# STM32F401R.net
KiCad netlist of a schematic drawn in Altium Designer
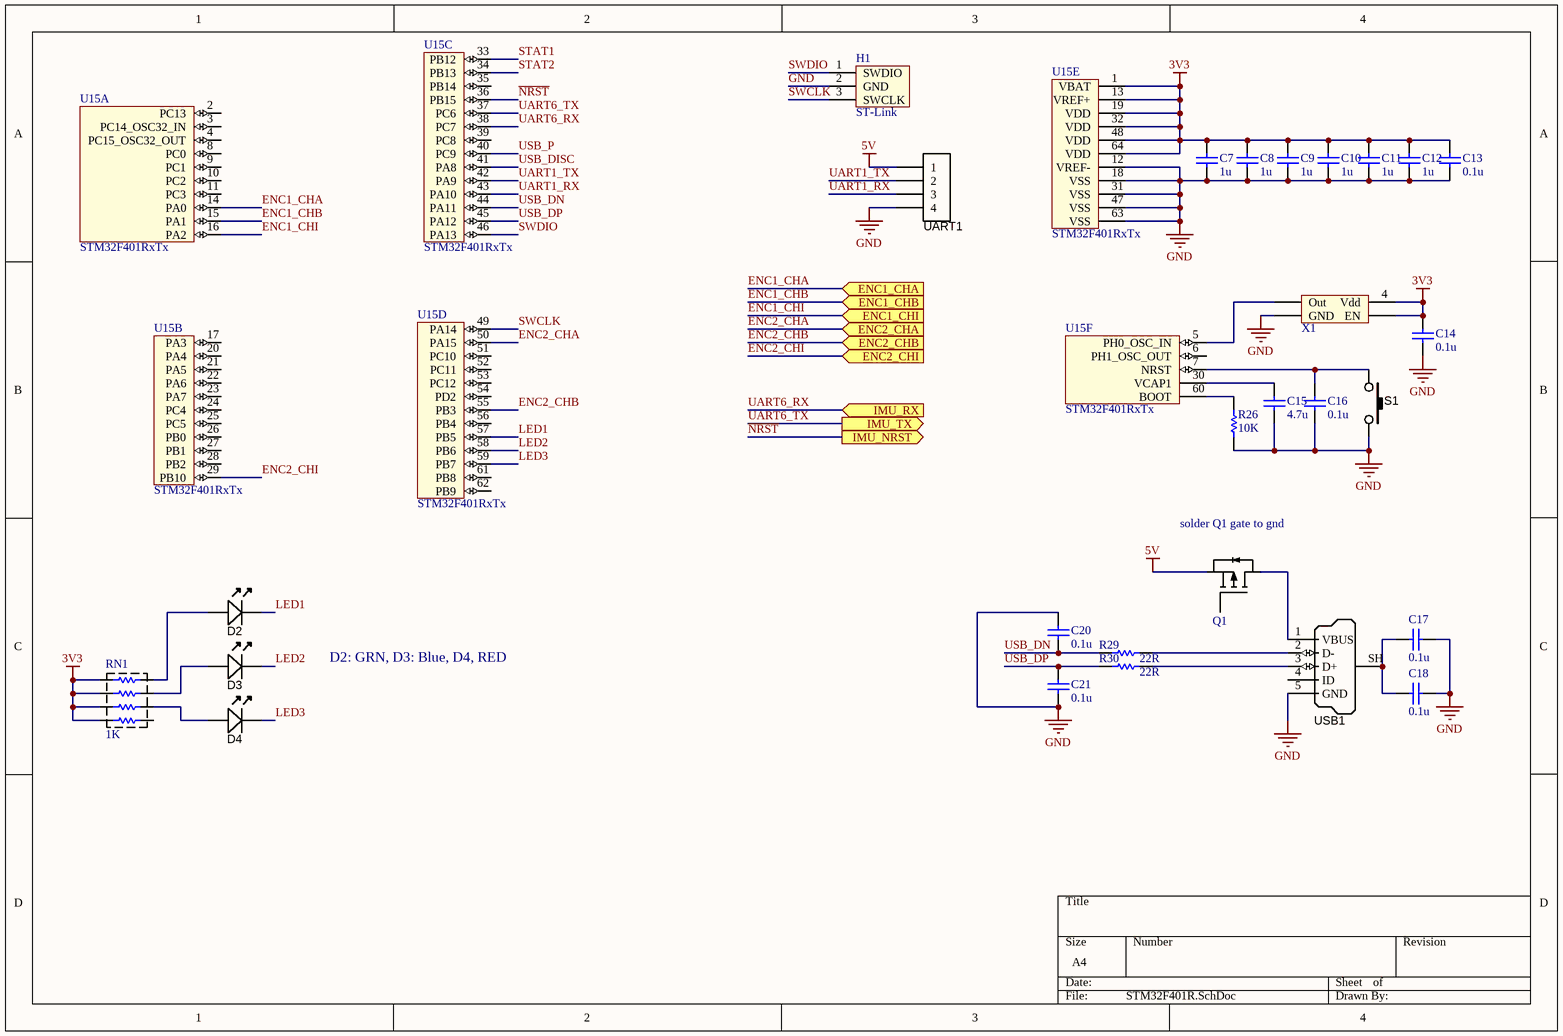
[diagram p0: STM32F401R.SchDoc]

(export (version "E")
  (design (tool "Eeschema 10.0.6"))
  (components
    (comp (ref "C7")
      (value "1u")
      (footprint "CAPC1608X90N")
      (description "Capacitor")
      (fields (field (name "Comment") "Cap") (field (name "PUBLISHER") "Altium Limited"))
      (libsource (lib "IOBoard_Low") (part "Cap"))
    )
    (comp (ref "C8")
      (value "1u")
      (footprint "CAPC1608X90N")
      (description "Capacitor")
      (fields (field (name "Comment") "Cap") (field (name "PUBLISHER") "Altium Limited"))
      (libsource (lib "IOBoard_Low") (part "Cap"))
    )
    (comp (ref "C9")
      (value "1u")
      (footprint "CAPC1608X90N")
      (description "Capacitor")
      (fields (field (name "Comment") "Cap") (field (name "PUBLISHER") "Altium Limited"))
      (libsource (lib "IOBoard_Low") (part "Cap"))
    )
    (comp (ref "C10")
      (value "1u")
      (footprint "CAPC1608X90N")
      (description "Capacitor")
      (fields (field (name "Comment") "Cap") (field (name "PUBLISHER") "Altium Limited"))
      (libsource (lib "IOBoard_Low") (part "Cap"))
    )
    (comp (ref "C11")
      (value "1u")
      (footprint "CAPC1608X90N")
      (description "Capacitor")
      (fields (field (name "Comment") "Cap") (field (name "PUBLISHER") "Altium Limited"))
      (libsource (lib "IOBoard_Low") (part "Cap"))
    )
    (comp (ref "C12")
      (value "1u")
      (footprint "CAPC1608X90N")
      (description "Capacitor")
      (fields (field (name "Comment") "Cap") (field (name "PUBLISHER") "Altium Limited"))
      (libsource (lib "IOBoard_Low") (part "Cap"))
    )
    (comp (ref "C13")
      (value "0.1u")
      (footprint "CAPC1608X90N")
      (description "Capacitor")
      (fields (field (name "Comment") "Cap") (field (name "PUBLISHER") "Altium Limited"))
      (libsource (lib "IOBoard_Low") (part "Cap"))
    )
    (comp (ref "C14")
      (value "0.1u")
      (footprint "CAPC1608X90N")
      (description "Capacitor")
      (fields (field (name "Comment") "Cap") (field (name "PUBLISHER") "Altium Limited"))
      (libsource (lib "IOBoard_Low") (part "Cap"))
    )
    (comp (ref "C15")
      (value "4.7u")
      (footprint "CAPC1608X90N")
      (description "Capacitor")
      (fields (field (name "Comment") "Cap") (field (name "PUBLISHER") "Altium Limited"))
      (libsource (lib "IOBoard_Low") (part "Cap"))
    )
    (comp (ref "C16")
      (value "0.1u")
      (footprint "CAPC1608X90N")
      (description "Capacitor")
      (fields (field (name "Comment") "Cap") (field (name "PUBLISHER") "Altium Limited"))
      (libsource (lib "IOBoard_Low") (part "Cap"))
    )
    (comp (ref "C17")
      (value "0.1u")
      (footprint "CAPC1608X90N")
      (description "Capacitor")
      (fields (field (name "Comment") "Cap") (field (name "PUBLISHER") "Altium Limited"))
      (libsource (lib "IOBoard_Low") (part "Cap"))
    )
    (comp (ref "C18")
      (value "0.1u")
      (footprint "CAPC1608X90N")
      (description "Capacitor")
      (fields (field (name "Comment") "Cap") (field (name "PUBLISHER") "Altium Limited"))
      (libsource (lib "IOBoard_Low") (part "Cap"))
    )
    (comp (ref "C20")
      (value "0.1u")
      (footprint "CAPC1608X90N")
      (description "Capacitor")
      (fields (field (name "Comment") "Cap") (field (name "PUBLISHER") "Altium Limited"))
      (libsource (lib "IOBoard_Low") (part "Cap"))
    )
    (comp (ref "C21")
      (value "0.1u")
      (footprint "CAPC1608X90N")
      (description "Capacitor")
      (fields (field (name "Comment") "Cap") (field (name "PUBLISHER") "Altium Limited"))
      (libsource (lib "IOBoard_Low") (part "Cap"))
    )
    (comp (ref "D2")
      (value "LED_Green_GullWing")
      (footprint "LED-0805-A")
      (description "LED Gull-wing SMD High-intensity Green 450mcd 574nm")
      (libsource (lib "IOBoard") (part "LED_Green_GullWing"))
    )
    (comp (ref "D3")
      (value "LED_Green_GullWing")
      (footprint "LED-0805-A")
      (description "LED Gull-wing SMD High-intensity Green 450mcd 574nm")
      (libsource (lib "IOBoard") (part "LED_Green_GullWing"))
    )
    (comp (ref "D4")
      (value "LED_Green_GullWing")
      (footprint "LED-0805-A")
      (description "LED Gull-wing SMD High-intensity Green 450mcd 574nm")
      (libsource (lib "IOBoard") (part "LED_Green_GullWing"))
    )
    (comp (ref "H1")
      (value "ST-Link")
      (footprint "ST-Link")
      (description "ST-Link header with silkscreen")
      (libsource (lib "IOBoard") (part "ST-Link"))
    )
    (comp (ref "Q1")
      (value "DMP4010SK3Q")
      (footprint "TO-252")
      (libsource (lib "IOBoard_Low") (part "DMP4010SK3Q"))
    )
    (comp (ref "R26")
      (value "10K")
      (footprint "RESC1608X55N")
      (description "Resistor")
      (fields (field (name "Comment") "Res1") (field (name "PUBLISHER") "Altium Limited"))
      (libsource (lib "IOBoard_Low") (part "Res1"))
    )
    (comp (ref "R29")
      (value "22R")
      (footprint "RESC1608X55N")
      (description "Resistor")
      (fields (field (name "Comment") "Res1") (field (name "PUBLISHER") "Altium Limited"))
      (libsource (lib "IOBoard_Low") (part "Res1"))
    )
    (comp (ref "R30")
      (value "22R")
      (footprint "RESC1608X55N")
      (description "Resistor")
      (fields (field (name "Comment") "Res1") (field (name "PUBLISHER") "Altium Limited"))
      (libsource (lib "IOBoard_Low") (part "Res1"))
    )
    (comp (ref "RN1")
      (value "1K")
      (footprint "RESCAXS50P160X320X70-8N")
      (fields (field (name "Comment") "resistor network"))
      (libsource (lib "IOBoard") (part "RES_NET"))
    )
    (comp (ref "S1")
      (value "SW_THT_PB_4.3mm")
      (footprint "TACT_SWT-SMD-4.4")
      (description "Switch, tact, 4.3mm stem")
      (libsource (lib "IOBoard") (part "SW_THT_PB_4.3mm"))
    )
    (comp (ref "U15")
      (value "STM32F401RxTx")
      (footprint "LQFP64")
      (libsource (lib "IOBoard") (part "STM32F401RxTx"))
    )
    (comp (ref "UART1")
      (value "Programmer")
      (footprint "HDR1X4_2.54MMP")
      (description "Header 4-pin")
      (libsource (lib "IOBoard") (part "Header4P"))
    )
    (comp (ref "USB1")
      (value "USB Micro Type B")
      (footprint "USB_MICRO-B")
      (description "Connector SMD USB Micro Type B middle mount")
      (libsource (lib "IOBoard") (part "USB_Micro_TypeB"))
    )
    (comp (ref "X1")
      (value "ASV-8.000MHZ-EJ-T")
      (footprint "ASV SERIES")
      (description "3.3Vdc HCMOS SMD Crystal Clock Oscillator")
      (fields (field (name "MANUFACTURER") "Abracon"))
      (libsource (lib "IOBoard") (part "ASV-8.000MHZ-EJ-T"))
    )
  )
  (nets
    (net (code "1") (name "/ENC1_CHA") (class "Default")
      (node (ref "U15") (pin "14") (pinfunction "PA0_14") (pintype "bidirectional"))
    )
    (net (code "2") (name "/ENC1_CHB") (class "Default")
      (node (ref "U15") (pin "15") (pinfunction "PA1_15") (pintype "bidirectional"))
    )
    (net (code "3") (name "/ENC1_CHI") (class "Default")
      (node (ref "U15") (pin "16") (pinfunction "PA2_16") (pintype "bidirectional"))
    )
    (net (code "4") (name "/ENC2_CHA") (class "Default")
      (node (ref "U15") (pin "50") (pinfunction "PA15_50") (pintype "bidirectional"))
    )
    (net (code "5") (name "/ENC2_CHB") (class "Default")
      (node (ref "U15") (pin "55") (pinfunction "PB3_55") (pintype "bidirectional"))
    )
    (net (code "6") (name "/ENC2_CHI") (class "Default")
      (node (ref "U15") (pin "29") (pinfunction "PB10_29") (pintype "bidirectional"))
    )
    (net (code "7") (name "/LED1") (class "Default")
      (node (ref "D2") (pin "K") (pinfunction "K_K") (pintype "passive"))
      (node (ref "U15") (pin "57") (pinfunction "PB5_57") (pintype "bidirectional"))
    )
    (net (code "8") (name "/LED2") (class "Default")
      (node (ref "D3") (pin "K") (pinfunction "K_K") (pintype "passive"))
      (node (ref "U15") (pin "58") (pinfunction "PB6_58") (pintype "bidirectional"))
    )
    (net (code "9") (name "/LED3") (class "Default")
      (node (ref "D4") (pin "K") (pinfunction "K_K") (pintype "passive"))
      (node (ref "U15") (pin "59") (pinfunction "PB7_59") (pintype "bidirectional"))
    )
    (net (code "10") (name "/STAT1") (class "Default")
      (node (ref "U15") (pin "33") (pinfunction "PB12_33") (pintype "bidirectional"))
    )
    (net (code "11") (name "/STAT2") (class "Default")
      (node (ref "U15") (pin "34") (pinfunction "PB13_34") (pintype "bidirectional"))
    )
    (net (code "12") (name "/SWCLK") (class "Default")
      (node (ref "H1") (pin "3") (pinfunction "SWCLK_3") (pintype "power_in"))
      (node (ref "U15") (pin "49") (pinfunction "PA14_49") (pintype "bidirectional"))
    )
    (net (code "13") (name "/SWDIO") (class "Default")
      (node (ref "H1") (pin "1") (pinfunction "SWDIO_1") (pintype "power_in"))
      (node (ref "U15") (pin "46") (pinfunction "PA13_46") (pintype "bidirectional"))
    )
    (net (code "14") (name "/UART1_RX") (class "Default")
      (node (ref "U15") (pin "43") (pinfunction "PA10_43") (pintype "bidirectional"))
      (node (ref "UART1") (pin "3") (pinfunction "3_3") (pintype "passive"))
    )
    (net (code "15") (name "/UART1_TX") (class "Default")
      (node (ref "U15") (pin "42") (pinfunction "PA9_42") (pintype "bidirectional"))
      (node (ref "UART1") (pin "2") (pinfunction "2_2") (pintype "passive"))
    )
    (net (code "16") (name "/UART6_RX") (class "Default")
      (node (ref "U15") (pin "38") (pinfunction "PC7_38") (pintype "bidirectional"))
    )
    (net (code "17") (name "/UART6_TX") (class "Default")
      (node (ref "U15") (pin "37") (pinfunction "PC6_37") (pintype "bidirectional"))
    )
    (net (code "18") (name "/USB_DISC") (class "Default")
      (node (ref "U15") (pin "41") (pinfunction "PA8_41") (pintype "bidirectional"))
    )
    (net (code "19") (name "/USB_DN") (class "Default")
      (node (ref "C20") (pin "1") (pinfunction "1_1") (pintype "passive"))
      (node (ref "R29") (pin "1") (pinfunction "1_1") (pintype "passive"))
      (node (ref "U15") (pin "44") (pinfunction "PA11_44") (pintype "bidirectional"))
    )
    (net (code "20") (name "/USB_DP") (class "Default")
      (node (ref "C21") (pin "2") (pinfunction "2_2") (pintype "passive"))
      (node (ref "R30") (pin "1") (pinfunction "1_1") (pintype "passive"))
      (node (ref "U15") (pin "45") (pinfunction "PA12_45") (pintype "bidirectional"))
    )
    (net (code "21") (name "/USB_P") (class "Default")
      (node (ref "U15") (pin "40") (pinfunction "PC9_40") (pintype "bidirectional"))
    )
    (net (code "22") (name "/~{NRST}") (class "Default")
      (node (ref "U15") (pin "36") (pinfunction "PB15_36") (pintype "bidirectional"))
    )
    (net (code "23") (name "3V3") (class "Default")
      (node (ref "C10") (pin "2") (pinfunction "2_2") (pintype "passive"))
      (node (ref "C11") (pin "2") (pinfunction "2_2") (pintype "passive"))
      (node (ref "C12") (pin "2") (pinfunction "2_2") (pintype "passive"))
      (node (ref "C13") (pin "2") (pinfunction "2_2") (pintype "passive"))
      (node (ref "C14") (pin "2") (pinfunction "2_2") (pintype "passive"))
      (node (ref "C7") (pin "2") (pinfunction "2_2") (pintype "passive"))
      (node (ref "C8") (pin "2") (pinfunction "2_2") (pintype "passive"))
      (node (ref "C9") (pin "2") (pinfunction "2_2") (pintype "passive"))
      (node (ref "RN1") (pin "1") (pinfunction "1_1") (pintype "power_in"))
      (node (ref "RN1") (pin "2") (pinfunction "2_2") (pintype "power_in"))
      (node (ref "RN1") (pin "3") (pinfunction "3_3") (pintype "power_in"))
      (node (ref "RN1") (pin "4") (pinfunction "4_4") (pintype "power_in"))
      (node (ref "U15") (pin "1") (pinfunction "VBAT_1") (pintype "power_in"))
      (node (ref "U15") (pin "13") (pinfunction "VREF+_13") (pintype "power_in"))
      (node (ref "U15") (pin "19") (pinfunction "VDD_19") (pintype "power_in"))
      (node (ref "U15") (pin "32") (pinfunction "VDD_32") (pintype "power_in"))
      (node (ref "U15") (pin "48") (pinfunction "VDD_48") (pintype "power_in"))
      (node (ref "U15") (pin "64") (pinfunction "VDD_64") (pintype "power_in"))
      (node (ref "X1") (pin "1") (pinfunction "EN_1") (pintype "passive"))
      (node (ref "X1") (pin "4") (pinfunction "Vdd_4") (pintype "passive"))
    )
    (net (code "24") (name "5V") (class "Default")
      (node (ref "Q1") (pin "3") (pinfunction "S_3") (pintype "passive"))
      (node (ref "UART1") (pin "1") (pinfunction "1_1") (pintype "passive"))
    )
    (net (code "25") (name "GND") (class "Default")
      (node (ref "C10") (pin "1") (pinfunction "1_1") (pintype "passive"))
      (node (ref "C11") (pin "1") (pinfunction "1_1") (pintype "passive"))
      (node (ref "C12") (pin "1") (pinfunction "1_1") (pintype "passive"))
      (node (ref "C13") (pin "1") (pinfunction "1_1") (pintype "passive"))
      (node (ref "C14") (pin "1") (pinfunction "1_1") (pintype "passive"))
      (node (ref "C15") (pin "1") (pinfunction "1_1") (pintype "passive"))
      (node (ref "C16") (pin "1") (pinfunction "1_1") (pintype "passive"))
      (node (ref "C17") (pin "2") (pinfunction "2_2") (pintype "passive"))
      (node (ref "C18") (pin "2") (pinfunction "2_2") (pintype "passive"))
      (node (ref "C20") (pin "2") (pinfunction "2_2") (pintype "passive"))
      (node (ref "C21") (pin "1") (pinfunction "1_1") (pintype "passive"))
      (node (ref "C7") (pin "1") (pinfunction "1_1") (pintype "passive"))
      (node (ref "C8") (pin "1") (pinfunction "1_1") (pintype "passive"))
      (node (ref "C9") (pin "1") (pinfunction "1_1") (pintype "passive"))
      (node (ref "H1") (pin "2") (pinfunction "GND_2") (pintype "power_in"))
      (node (ref "R26") (pin "1") (pinfunction "1_1") (pintype "passive"))
      (node (ref "S1") (pin "2") (pintype "passive"))
      (node (ref "U15") (pin "12") (pinfunction "VREF-_12") (pintype "power_in"))
      (node (ref "U15") (pin "18") (pinfunction "VSS_18") (pintype "power_in"))
      (node (ref "U15") (pin "31") (pinfunction "VSS_31") (pintype "power_in"))
      (node (ref "U15") (pin "47") (pinfunction "VSS_47") (pintype "power_in"))
      (node (ref "U15") (pin "63") (pinfunction "VSS_63") (pintype "power_in"))
      (node (ref "UART1") (pin "4") (pinfunction "4_4") (pintype "passive"))
      (node (ref "USB1") (pin "5") (pinfunction "GND_5") (pintype "power_in"))
      (node (ref "X1") (pin "2") (pinfunction "GND_2") (pintype "passive"))
    )
    (net (code "26") (name "Net-(D2-PadA)") (class "Default")
      (node (ref "D2") (pin "A") (pinfunction "A_A") (pintype "passive"))
      (node (ref "RN1") (pin "8") (pinfunction "8_8") (pintype "power_in"))
    )
    (net (code "27") (name "Net-(D3-PadA)") (class "Default")
      (node (ref "D3") (pin "A") (pinfunction "A_A") (pintype "passive"))
      (node (ref "RN1") (pin "7") (pinfunction "7_7") (pintype "power_in"))
    )
    (net (code "28") (name "Net-(D4-PadA)") (class "Default")
      (node (ref "D4") (pin "A") (pinfunction "A_A") (pintype "passive"))
      (node (ref "RN1") (pin "6") (pinfunction "6_6") (pintype "power_in"))
    )
    (net (code "29") (name "Net-(Q1-D)") (class "Default")
      (node (ref "Q1") (pin "4") (pinfunction "D_4") (pintype "passive"))
      (node (ref "USB1") (pin "1") (pinfunction "VBUS_1") (pintype "power_in"))
    )
    (net (code "30") (name "Net-(U15F-BOOT)") (class "Default")
      (node (ref "R26") (pin "2") (pinfunction "2_2") (pintype "passive"))
      (node (ref "U15") (pin "60") (pinfunction "BOOT_60") (pintype "power_in"))
    )
    (net (code "31") (name "Net-(U15F-NRST)") (class "Default")
      (node (ref "C16") (pin "2") (pinfunction "2_2") (pintype "passive"))
      (node (ref "S1") (pin "1") (pintype "passive"))
      (node (ref "U15") (pin "7") (pinfunction "NRST_7") (pintype "bidirectional"))
    )
    (net (code "32") (name "Net-(U15F-PH0_OSC_IN)") (class "Default")
      (node (ref "U15") (pin "5") (pinfunction "PH0_OSC_IN_5") (pintype "bidirectional"))
      (node (ref "X1") (pin "3") (pinfunction "Out_3") (pintype "passive"))
    )
    (net (code "33") (name "Net-(U15F-VCAP1)") (class "Default")
      (node (ref "C15") (pin "2") (pinfunction "2_2") (pintype "passive"))
      (node (ref "U15") (pin "30") (pinfunction "VCAP1_30") (pintype "power_in"))
    )
    (net (code "34") (name "Net-(USB1-D+)") (class "Default")
      (node (ref "R30") (pin "2") (pinfunction "2_2") (pintype "passive"))
      (node (ref "USB1") (pin "3") (pinfunction "D+_3") (pintype "bidirectional"))
    )
    (net (code "35") (name "Net-(USB1-D-)") (class "Default")
      (node (ref "R29") (pin "2") (pinfunction "2_2") (pintype "passive"))
      (node (ref "USB1") (pin "2") (pinfunction "D-_2") (pintype "bidirectional"))
    )
    (net (code "36") (name "Net-(USB1-Shell)") (class "Default")
      (node (ref "C17") (pin "1") (pinfunction "1_1") (pintype "passive"))
      (node (ref "C18") (pin "1") (pinfunction "1_1") (pintype "passive"))
      (node (ref "USB1") (pin "SH") (pinfunction "Shell_SH") (pintype "passive"))
    )
    (net (code "37") (name "unconnected-(Q1-G-Pad1)") (class "Default")
      (node (ref "Q1") (pin "1") (pinfunction "G_1") (pintype "passive"))
    )
    (net (code "38") (name "unconnected-(RN1-Pad5)") (class "Default")
      (node (ref "RN1") (pin "5") (pinfunction "5_5") (pintype "power_in"))
    )
    (net (code "39") (name "unconnected-(U15A-PC0-Pad8)") (class "Default")
      (node (ref "U15") (pin "8") (pinfunction "PC0_8") (pintype "bidirectional"))
    )
    (net (code "40") (name "unconnected-(U15A-PC1-Pad9)") (class "Default")
      (node (ref "U15") (pin "9") (pinfunction "PC1_9") (pintype "bidirectional"))
    )
    (net (code "41") (name "unconnected-(U15A-PC2-Pad10)") (class "Default")
      (node (ref "U15") (pin "10") (pinfunction "PC2_10") (pintype "bidirectional"))
    )
    (net (code "42") (name "unconnected-(U15A-PC3-Pad11)") (class "Default")
      (node (ref "U15") (pin "11") (pinfunction "PC3_11") (pintype "bidirectional"))
    )
    (net (code "43") (name "unconnected-(U15A-PC13-Pad2)") (class "Default")
      (node (ref "U15") (pin "2") (pinfunction "PC13_2") (pintype "bidirectional"))
    )
    (net (code "44") (name "unconnected-(U15A-PC14_OSC32_IN-Pad3)") (class "Default")
      (node (ref "U15") (pin "3") (pinfunction "PC14_OSC32_IN_3") (pintype "bidirectional"))
    )
    (net (code "45") (name "unconnected-(U15A-PC15_OSC32_OUT-Pad4)") (class "Default")
      (node (ref "U15") (pin "4") (pinfunction "PC15_OSC32_OUT_4") (pintype "bidirectional"))
    )
    (net (code "46") (name "unconnected-(U15B-PA3-Pad17)") (class "Default")
      (node (ref "U15") (pin "17") (pinfunction "PA3_17") (pintype "bidirectional"))
    )
    (net (code "47") (name "unconnected-(U15B-PA4-Pad20)") (class "Default")
      (node (ref "U15") (pin "20") (pinfunction "PA4_20") (pintype "bidirectional"))
    )
    (net (code "48") (name "unconnected-(U15B-PA5-Pad21)") (class "Default")
      (node (ref "U15") (pin "21") (pinfunction "PA5_21") (pintype "bidirectional"))
    )
    (net (code "49") (name "unconnected-(U15B-PA6-Pad22)") (class "Default")
      (node (ref "U15") (pin "22") (pinfunction "PA6_22") (pintype "bidirectional"))
    )
    (net (code "50") (name "unconnected-(U15B-PA7-Pad23)") (class "Default")
      (node (ref "U15") (pin "23") (pinfunction "PA7_23") (pintype "bidirectional"))
    )
    (net (code "51") (name "unconnected-(U15B-PB0-Pad26)") (class "Default")
      (node (ref "U15") (pin "26") (pinfunction "PB0_26") (pintype "bidirectional"))
    )
    (net (code "52") (name "unconnected-(U15B-PB1-Pad27)") (class "Default")
      (node (ref "U15") (pin "27") (pinfunction "PB1_27") (pintype "bidirectional"))
    )
    (net (code "53") (name "unconnected-(U15B-PB2-Pad28)") (class "Default")
      (node (ref "U15") (pin "28") (pinfunction "PB2_28") (pintype "bidirectional"))
    )
    (net (code "54") (name "unconnected-(U15B-PC4-Pad24)") (class "Default")
      (node (ref "U15") (pin "24") (pinfunction "PC4_24") (pintype "bidirectional"))
    )
    (net (code "55") (name "unconnected-(U15B-PC5-Pad25)") (class "Default")
      (node (ref "U15") (pin "25") (pinfunction "PC5_25") (pintype "bidirectional"))
    )
    (net (code "56") (name "unconnected-(U15C-PB14-Pad35)") (class "Default")
      (node (ref "U15") (pin "35") (pinfunction "PB14_35") (pintype "bidirectional"))
    )
    (net (code "57") (name "unconnected-(U15C-PC8-Pad39)") (class "Default")
      (node (ref "U15") (pin "39") (pinfunction "PC8_39") (pintype "bidirectional"))
    )
    (net (code "58") (name "unconnected-(U15D-PB4-Pad56)") (class "Default")
      (node (ref "U15") (pin "56") (pinfunction "PB4_56") (pintype "bidirectional"))
    )
    (net (code "59") (name "unconnected-(U15D-PB8-Pad61)") (class "Default")
      (node (ref "U15") (pin "61") (pinfunction "PB8_61") (pintype "bidirectional"))
    )
    (net (code "60") (name "unconnected-(U15D-PB9-Pad62)") (class "Default")
      (node (ref "U15") (pin "62") (pinfunction "PB9_62") (pintype "bidirectional"))
    )
    (net (code "61") (name "unconnected-(U15D-PC10-Pad51)") (class "Default")
      (node (ref "U15") (pin "51") (pinfunction "PC10_51") (pintype "bidirectional"))
    )
    (net (code "62") (name "unconnected-(U15D-PC11-Pad52)") (class "Default")
      (node (ref "U15") (pin "52") (pinfunction "PC11_52") (pintype "bidirectional"))
    )
    (net (code "63") (name "unconnected-(U15D-PC12-Pad53)") (class "Default")
      (node (ref "U15") (pin "53") (pinfunction "PC12_53") (pintype "bidirectional"))
    )
    (net (code "64") (name "unconnected-(U15D-PD2-Pad54)") (class "Default")
      (node (ref "U15") (pin "54") (pinfunction "PD2_54") (pintype "bidirectional"))
    )
    (net (code "65") (name "unconnected-(U15F-PH1_OSC_OUT-Pad6)") (class "Default")
      (node (ref "U15") (pin "6") (pinfunction "PH1_OSC_OUT_6") (pintype "bidirectional"))
    )
    (net (code "66") (name "unconnected-(USB1-ID-Pad4)") (class "Default")
      (node (ref "USB1") (pin "4") (pinfunction "ID_4") (pintype "passive"))
    )
  )
)
